# SIM808_RF.net
KiCad netlist of a schematic drawn in Altium Designer
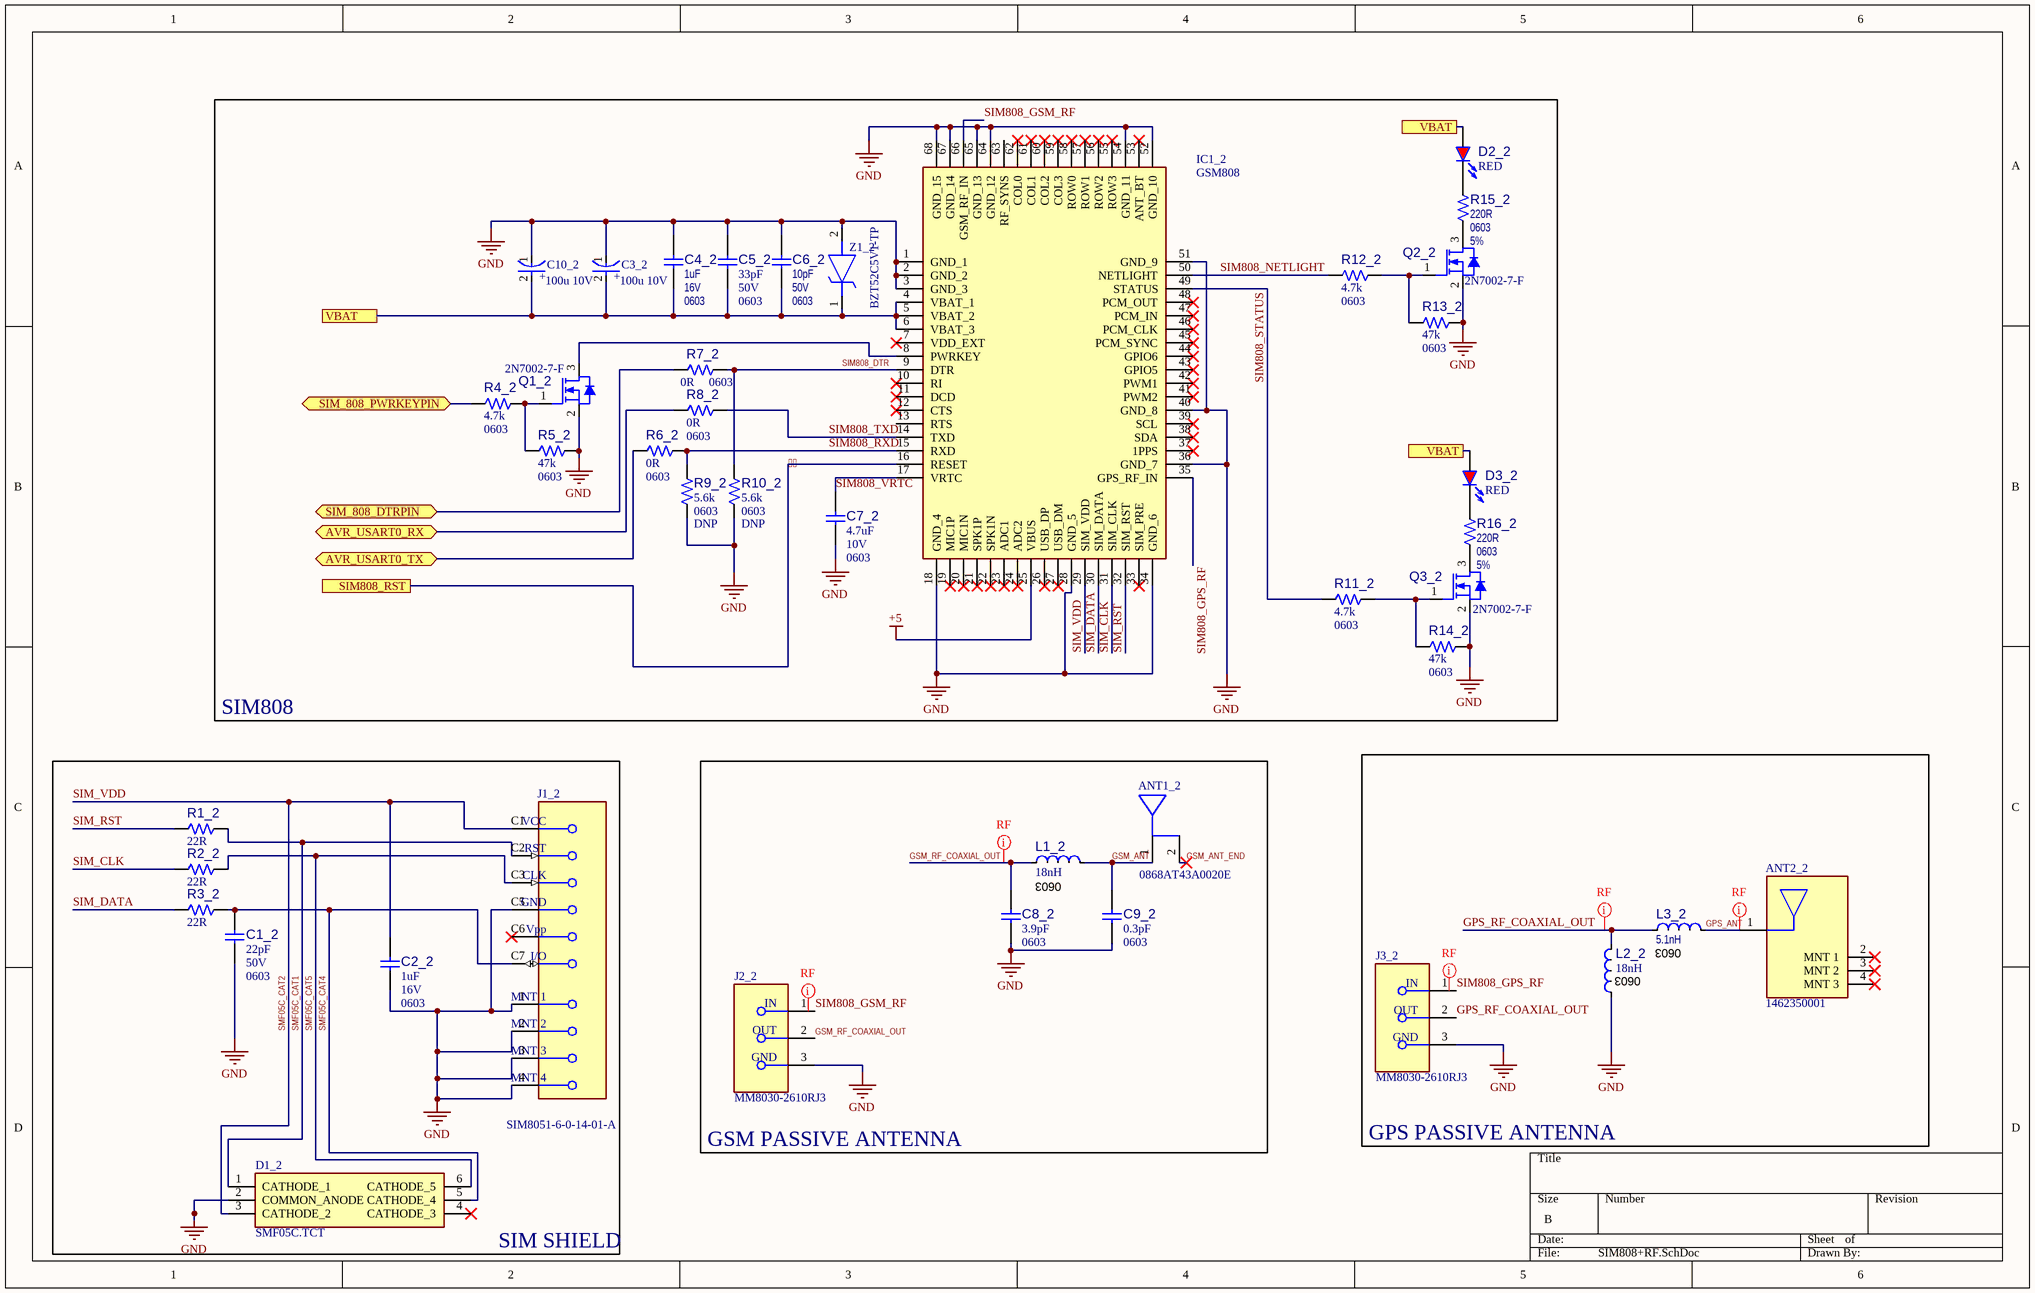
[diagram p0: SIM808+RF.SchDoc]

(export (version "E")
  (design (tool "Eeschema 10.0.6"))
  (components
    (comp (ref "ANT1_2")
      (value "0868AT43A0020E")
      (footprint "FP-0900AT43A0070E-MFG")
      (description "RF ANT CHIP SOLDER SMD")
      (libsource (lib "Altium Content Vault") (part "fdeedc8c81902f4dca238edc9264297"))
    )
    (comp (ref "ANT2_2")
      (value "1462350001")
      (footprint "FP-1462350001-MFG")
      (description "RF ANT 1.575GHZ MOLDED SLDR SMD")
      (fields
        (field (name "OCTOPART") "https://octopart.com/146235-0001-molex-75198029")
        (field (name "MANUFACTURER") "Molex")
      )
      (libsource (lib "Altium Content Vault") (part "44fa71a15c7cd8753818309cfbbf304"))
    )
    (comp (ref "C1_2")
      (value "22pF")
      (footprint "CAP_C_0603")
      (fields
        (field (name "VOLTAGE") "50V")
        (field (name "PACKAGE") "0603")
        (field (name "TOLERANCE") "5%")
        (field (name "Comment") "Capacitor NP")
      )
      (libsource (lib "MCHP-CDB") (part "Capacitor NP"))
    )
    (comp (ref "C2_2")
      (value "1uF")
      (footprint "CAP_C_0603")
      (fields
        (field (name "VOLTAGE") "16V")
        (field (name "PACKAGE") "0603")
        (field (name "TOLERANCE") "10%")
        (field (name "Comment") "Capacitor NP")
      )
      (libsource (lib "MCHP-CDB") (part "Capacitor NP"))
    )
    (comp (ref "C3_2")
      (value "100u 10V")
      (footprint "FP-TAJC-MFG")
      (description "100uF 10V  ±10% 1.2Ω 2312  SMD Tantalum Capacitor")
      (fields (field (name "TOLERANCE") "10%") (field (name "VOLTAGE") "10V"))
      (libsource (lib "Altium Content Vault") (part "203bc49f2ac43e59fd269a8c329ed05"))
    )
    (comp (ref "C4_2")
      (value "1uF")
      (footprint "CAP_C_0603")
      (fields
        (field (name "VOLTAGE") "16V")
        (field (name "PACKAGE") "0603")
        (field (name "TOLERANCE") "10%")
        (field (name "Comment") "Capacitor NP")
      )
      (libsource (lib "MCHP-CDB") (part "Capacitor NP"))
    )
    (comp (ref "C5_2")
      (value "33pF")
      (footprint "CAP_C_0603")
      (fields
        (field (name "VOLTAGE") "50V")
        (field (name "PACKAGE") "0603")
        (field (name "TOLERANCE") "5%")
        (field (name "Comment") "Capacitor NP")
      )
      (libsource (lib "MCHP-CDB") (part "Capacitor NP"))
    )
    (comp (ref "C6_2")
      (value "10pF")
      (footprint "CAP_C_0603")
      (fields
        (field (name "VOLTAGE") "50V")
        (field (name "PACKAGE") "0603")
        (field (name "TOLERANCE") "0.5pF")
        (field (name "Comment") "Capacitor NP")
        (field (name "OWNER") "Leah Whitaker")
      )
      (libsource (lib "MCHP-CDB") (part "Capacitor NP"))
    )
    (comp (ref "C7_2")
      (value "4.7uF")
      (footprint "CAP_C_0603")
      (fields
        (field (name "VOLTAGE") "10V")
        (field (name "PACKAGE") "0603")
        (field (name "TOLERANCE") "80%")
        (field (name "Comment") "Capacitor NP")
      )
      (libsource (lib "MCHP-CDB") (part "Capacitor NP"))
    )
    (comp (ref "C8_2")
      (value "3.9pF")
      (footprint "CAP_C_0603")
      (fields
        (field (name "PACKAGE") "0603")
        (field (name "TOLERANCE") "0.25pF")
        (field (name "Comment") "Capacitor NP")
      )
      (libsource (lib "MCHP-CDB") (part "Capacitor NP"))
    )
    (comp (ref "C9_2")
      (value "0.3pF")
      (footprint "CAP_C_0603")
      (fields
        (field (name "PACKAGE") "0603")
        (field (name "TOLERANCE") "0.25pF")
        (field (name "Comment") "Capacitor NP")
      )
      (libsource (lib "MCHP-CDB") (part "Capacitor NP"))
    )
    (comp (ref "C10_2")
      (value "100u 10V")
      (footprint "FP-TAJC-MFG")
      (description "100uF 10V  ±10% 1.2Ω 2312  SMD Tantalum Capacitor")
      (fields (field (name "TOLERANCE") "10%") (field (name "VOLTAGE") "10V"))
      (libsource (lib "Altium Content Vault") (part "203bc49f2ac43e59fd269a8c329ed05"))
    )
    (comp (ref "D1_2")
      (value "SMF05C.TCT")
      (footprint "SamacSys:SOT65P210X110-6N")
      (description "TVS Diode (Uni-directional)")
      (fields (field (name "MOUSER PART NUMBER") "947-SMF05C.TCT"))
      (libsource (lib "*") (part "SMF05C.TCT"))
    )
    (comp (ref "D2_2")
      (value "RED")
      (footprint "LED_0603_RED")
      (description "LED")
      (fields (field (name "POWER") "100mW") (field (name "Comment") "LED_red"))
      (libsource (lib "MCHP-CDB") (part "LED_red"))
    )
    (comp (ref "D3_2")
      (value "RED")
      (footprint "LED_0603_RED")
      (description "LED")
      (fields (field (name "POWER") "100mW") (field (name "Comment") "LED_red"))
      (libsource (lib "MCHP-CDB") (part "LED_red"))
    )
    (comp (ref "IC1_2")
      (value "GSM808")
      (footprint "SamacSys:GSM808")
      (description "Integrated Circuit")
      (libsource (lib "*") (part "GSM808"))
    )
    (comp (ref "J1_2")
      (value "SIM8051-6-0-14-01-A")
      (footprint "FP-SIM8051-6-0-14-01-A-MFG")
      (description "NANO SIM PUSH PULL, 6P, SMT, 1.3")
      (fields
        (field (name "MANUFACTURER") "GCT")
        (field (name "OCTOPART") "https://octopart.com/sim8051-6-0-14-01-a-gct-99340323")
      )
      (libsource (lib "Altium Content Vault") (part "3cc3b1fb44b6b07564fa90550f448b7"))
    )
    (comp (ref "J2_2")
      (value "MM8030-2610RJ3")
      (footprint "FP-MM8030-2610RJ3-MFG")
      (description "CONN SWG RCPT STR 50 OHM SMD")
      (libsource (lib "Altium Content Vault") (part "d3d0eca1eedd57daa0a06598d6096e1"))
    )
    (comp (ref "J3_2")
      (value "MM8030-2610RJ3")
      (footprint "FP-MM8030-2610RJ3-MFG")
      (description "CONN SWG RCPT STR 50 OHM SMD")
      (libsource (lib "Altium Content Vault") (part "d3d0eca1eedd57daa0a06598d6096e1"))
    )
    (comp (ref "L1_2")
      (value "18nH")
      (footprint "IND_C_0603")
      (description "Inductor")
      (libsource (lib "MCHP-CDB") (part "Inductor"))
    )
    (comp (ref "L2_2")
      (value "18nH")
      (footprint "IND_C_0603")
      (description "Inductor")
      (libsource (lib "MCHP-CDB") (part "Inductor"))
    )
    (comp (ref "L3_2")
      (value "5.1nH")
      (footprint "IND_C_0603")
      (description "Inductor")
      (fields (field (name "OWNER") "Gabor Bihari"))
      (libsource (lib "MCHP-CDB") (part "Inductor"))
    )
    (comp (ref "Q1_2")
      (value "2N7002-7-F")
      (footprint "SOT-23-3")
      (description "Transistor MOS")
      (fields
        (field (name "POWER") "370mW")
        (field (name "Comment") "Transistor MOS-N GSD")
        (field (name "OWNER") "Adrian M (M91404)")
      )
      (libsource (lib "MCHP-CDB") (part "Transistor MOS-N GSD"))
    )
    (comp (ref "Q2_2")
      (value "2N7002-7-F")
      (footprint "SOT-23-3")
      (description "Transistor MOS")
      (fields
        (field (name "POWER") "370mW")
        (field (name "Comment") "Transistor MOS-N GSD")
        (field (name "OWNER") "Adrian M (M91404)")
      )
      (libsource (lib "MCHP-CDB") (part "Transistor MOS-N GSD"))
    )
    (comp (ref "Q3_2")
      (value "2N7002-7-F")
      (footprint "SOT-23-3")
      (description "Transistor MOS")
      (fields
        (field (name "POWER") "370mW")
        (field (name "Comment") "Transistor MOS-N GSD")
        (field (name "OWNER") "Adrian M (M91404)")
      )
      (libsource (lib "MCHP-CDB") (part "Transistor MOS-N GSD"))
    )
    (comp (ref "R1_2")
      (value "22R")
      (footprint "RES_C_0603")
      (description "Resistor")
      (fields (field (name "VOLTAGE") "75V") (field (name "POWER") "1/10W"))
      (libsource (lib "MCHP-CDB") (part "Resistor"))
    )
    (comp (ref "R2_2")
      (value "22R")
      (footprint "RES_C_0603")
      (description "Resistor")
      (fields (field (name "VOLTAGE") "75V") (field (name "POWER") "1/10W"))
      (libsource (lib "MCHP-CDB") (part "Resistor"))
    )
    (comp (ref "R3_2")
      (value "22R")
      (footprint "RES_C_0603")
      (description "Resistor")
      (fields (field (name "VOLTAGE") "75V") (field (name "POWER") "1/10W"))
      (libsource (lib "MCHP-CDB") (part "Resistor"))
    )
    (comp (ref "R4_2")
      (value "4.7k")
      (footprint "RES_C_0603")
      (description "Resistor")
      (fields
        (field (name "PACKAGE") "0603")
        (field (name "VOLTAGE") "75V")
        (field (name "POWER") "1/10W")
        (field (name "OWNER") "Bogdan P (M91398)")
      )
      (libsource (lib "MCHP-CDB") (part "Resistor"))
    )
    (comp (ref "R5_2")
      (value "47k")
      (footprint "RES_C_0603")
      (description "Resistor")
      (fields
        (field (name "PACKAGE") "0603")
        (field (name "VOLTAGE") "75V")
        (field (name "POWER") "1/10W")
        (field (name "OWNER") "Adrian M (M91404)")
      )
      (libsource (lib "MCHP-CDB") (part "Resistor"))
    )
    (comp (ref "R6_2")
      (value "0R")
      (footprint "RES_C_0603")
      (description "Resistor")
      (fields
        (field (name "PACKAGE") "0603")
        (field (name "POWER") "1/10W")
        (field (name "OWNER") "Steve Dziaba")
      )
      (libsource (lib "MCHP-CDB") (part "Resistor"))
    )
    (comp (ref "R7_2")
      (value "0R")
      (footprint "RES_C_0603")
      (description "Resistor")
      (fields
        (field (name "PACKAGE") "0603")
        (field (name "POWER") "1/10W")
        (field (name "OWNER") "Steve Dziaba")
      )
      (libsource (lib "MCHP-CDB") (part "Resistor"))
    )
    (comp (ref "R8_2")
      (value "0R")
      (footprint "RES_C_0603")
      (description "Resistor")
      (fields
        (field (name "PACKAGE") "0603")
        (field (name "POWER") "1/10W")
        (field (name "OWNER") "Steve Dziaba")
      )
      (libsource (lib "MCHP-CDB") (part "Resistor"))
    )
    (comp (ref "R9_2")
      (value "5.6k")
      (footprint "RES_C_0603")
      (description "Resistor")
      (fields
        (field (name "PACKAGE") "0603")
        (field (name "VOLTAGE") "50V")
        (field (name "POWER") "1/10W")
        (field (name "POPULATED") "DNP")
      )
      (libsource (lib "MCHP-CDB") (part "Resistor"))
    )
    (comp (ref "R10_2")
      (value "5.6k")
      (footprint "RES_C_0603")
      (description "Resistor")
      (fields
        (field (name "PACKAGE") "0603")
        (field (name "VOLTAGE") "50V")
        (field (name "POWER") "1/10W")
        (field (name "POPULATED") "DNP")
      )
      (libsource (lib "MCHP-CDB") (part "Resistor"))
    )
    (comp (ref "R11_2")
      (value "4.7k")
      (footprint "RES_C_0603")
      (description "Resistor")
      (fields
        (field (name "PACKAGE") "0603")
        (field (name "VOLTAGE") "75V")
        (field (name "POWER") "1/10W")
        (field (name "OWNER") "Bogdan P (M91398)")
      )
      (libsource (lib "MCHP-CDB") (part "Resistor"))
    )
    (comp (ref "R12_2")
      (value "4.7k")
      (footprint "RES_C_0603")
      (description "Resistor")
      (fields
        (field (name "PACKAGE") "0603")
        (field (name "VOLTAGE") "75V")
        (field (name "POWER") "1/10W")
        (field (name "OWNER") "Bogdan P (M91398)")
      )
      (libsource (lib "MCHP-CDB") (part "Resistor"))
    )
    (comp (ref "R13_2")
      (value "47k")
      (footprint "RES_C_0603")
      (description "Resistor")
      (fields
        (field (name "PACKAGE") "0603")
        (field (name "VOLTAGE") "75V")
        (field (name "POWER") "1/10W")
        (field (name "OWNER") "Adrian M (M91404)")
      )
      (libsource (lib "MCHP-CDB") (part "Resistor"))
    )
    (comp (ref "R14_2")
      (value "47k")
      (footprint "RES_C_0603")
      (description "Resistor")
      (fields
        (field (name "PACKAGE") "0603")
        (field (name "VOLTAGE") "75V")
        (field (name "POWER") "1/10W")
        (field (name "OWNER") "Adrian M (M91404)")
      )
      (libsource (lib "MCHP-CDB") (part "Resistor"))
    )
    (comp (ref "R15_2")
      (value "220R")
      (footprint "RES_C_0603")
      (description "Resistor")
      (fields
        (field (name "PACKAGE") "0603")
        (field (name "TOLERANCE") "5%")
        (field (name "VOLTAGE") "50V")
        (field (name "POWER") "1/10W")
      )
      (libsource (lib "MCHP-CDB") (part "Resistor"))
    )
    (comp (ref "R16_2")
      (value "220R")
      (footprint "RES_C_0603")
      (description "Resistor")
      (fields
        (field (name "PACKAGE") "0603")
        (field (name "TOLERANCE") "5%")
        (field (name "VOLTAGE") "50V")
        (field (name "POWER") "1/10W")
      )
      (libsource (lib "MCHP-CDB") (part "Resistor"))
    )
    (comp (ref "Z1_2")
      (value "BZT52C5V1-TP")
      (footprint "SamacSys:SOD3716X135N")
      (description "Zener Diode")
      (fields (field (name "MOUSER PART NUMBER") "833-BZT52C5V1-TP"))
      (libsource (lib "*") (part "BZT52C5V1-TP"))
    )
  )
  (nets
    (net (code "1") (name "+5") (class "Default")
      (node (ref "IC1_2") (pin "25") (pinfunction "VBUS_25") (pintype "passive"))
    )
    (net (code "2") (name "/") (class "Default")
      (node (ref "IC1_2") (pin "16") (pinfunction "RESET_16") (pintype "passive"))
    )
    (net (code "3") (name "/AVR_USART0_RX") (class "Default")
      (node (ref "R8_2") (pin "1") (pinfunction "1_1") (pintype "passive"))
    )
    (net (code "4") (name "/AVR_USART0_TX") (class "Default")
      (node (ref "R6_2") (pin "1") (pinfunction "1_1") (pintype "passive"))
    )
    (net (code "5") (name "/GPS_ANT") (class "Default")
      (node (ref "ANT2_2") (pin "1") (pinfunction "FEEDING_PAD_1") (pintype "passive"))
      (node (ref "L3_2") (pin "2") (pinfunction "F_2") (pintype "passive"))
    )
    (net (code "6") (name "/GPS_RF_COAXIAL_OUT") (class "Default")
      (node (ref "J3_2") (pin "2") (pinfunction "OUT_2") (pintype "passive"))
      (node (ref "L2_2") (pin "2") (pinfunction "F_2") (pintype "passive"))
      (node (ref "L3_2") (pin "1") (pinfunction "S_1") (pintype "passive"))
    )
    (net (code "7") (name "/GSM_ANT") (class "Default")
      (node (ref "ANT1_2") (pin "1") (pinfunction "RF_Feeding_Point_1") (pintype "passive"))
      (node (ref "C9_2") (pin "2") (pinfunction "2_2") (pintype "passive"))
      (node (ref "L1_2") (pin "2") (pinfunction "F_2") (pintype "passive"))
    )
    (net (code "8") (name "/GSM_ANT_END") (class "Default")
      (node (ref "ANT1_2") (pin "2") (pinfunction "To_trace_element_2") (pintype "passive+no_connect"))
    )
    (net (code "9") (name "/GSM_RF_COAXIAL_OUT") (class "Default")
      (node (ref "C8_2") (pin "2") (pinfunction "2_2") (pintype "passive"))
      (node (ref "J2_2") (pin "2") (pinfunction "OUT_2") (pintype "passive"))
      (node (ref "L1_2") (pin "1") (pinfunction "S_1") (pintype "passive"))
    )
    (net (code "10") (name "/SIM808_DTR") (class "Default")
      (node (ref "IC1_2") (pin "9") (pinfunction "DTR_9") (pintype "passive"))
      (node (ref "R10_2") (pin "2") (pinfunction "2_2") (pintype "passive"))
      (node (ref "R7_2") (pin "2") (pinfunction "2_2") (pintype "passive"))
    )
    (net (code "11") (name "/SIM808_GPS_RF") (class "Default")
      (node (ref "IC1_2") (pin "35") (pinfunction "GPS_RF_IN_35") (pintype "passive"))
      (node (ref "J3_2") (pin "1") (pinfunction "IN_1") (pintype "passive"))
    )
    (net (code "12") (name "/SIM808_GSM_RF") (class "Default")
      (node (ref "IC1_2") (pin "66") (pinfunction "GSM_RF_IN_66") (pintype "passive"))
      (node (ref "J2_2") (pin "1") (pinfunction "IN_1") (pintype "passive"))
    )
    (net (code "13") (name "/SIM808_NETLIGHT") (class "Default")
      (node (ref "IC1_2") (pin "50") (pinfunction "NETLIGHT_50") (pintype "passive"))
      (node (ref "R12_2") (pin "1") (pinfunction "1_1") (pintype "passive"))
    )
    (net (code "14") (name "/SIM808_RXD") (class "Default")
      (node (ref "IC1_2") (pin "15") (pinfunction "RXD_15") (pintype "passive"))
      (node (ref "R6_2") (pin "2") (pinfunction "2_2") (pintype "passive"))
      (node (ref "R9_2") (pin "2") (pinfunction "2_2") (pintype "passive"))
    )
    (net (code "15") (name "/SIM808_STATUS") (class "Default")
      (node (ref "IC1_2") (pin "49") (pinfunction "STATUS_49") (pintype "passive"))
      (node (ref "R11_2") (pin "1") (pinfunction "1_1") (pintype "passive"))
    )
    (net (code "16") (name "/SIM808_TXD") (class "Default")
      (node (ref "IC1_2") (pin "14") (pinfunction "TXD_14") (pintype "passive"))
      (node (ref "R8_2") (pin "2") (pinfunction "2_2") (pintype "passive"))
    )
    (net (code "17") (name "/SIM808_VRTC") (class "Default")
      (node (ref "C7_2") (pin "2") (pinfunction "2_2") (pintype "passive"))
      (node (ref "IC1_2") (pin "17") (pinfunction "VRTC_17") (pintype "passive"))
    )
    (net (code "18") (name "/SIM_808_DTRPIN") (class "Default")
      (node (ref "R7_2") (pin "1") (pinfunction "1_1") (pintype "passive"))
    )
    (net (code "19") (name "/SIM_808_PWRKEYPIN") (class "Default")
      (node (ref "R4_2") (pin "1") (pinfunction "1_1") (pintype "passive"))
    )
    (net (code "20") (name "/SIM_CLK") (class "Default")
      (node (ref "IC1_2") (pin "31") (pinfunction "SIM_CLK_31") (pintype "passive"))
      (node (ref "R2_2") (pin "1") (pinfunction "1_1") (pintype "passive"))
    )
    (net (code "21") (name "/SIM_DATA") (class "Default")
      (node (ref "IC1_2") (pin "30") (pinfunction "SIM_DATA_30") (pintype "passive"))
      (node (ref "R3_2") (pin "1") (pinfunction "1_1") (pintype "passive"))
    )
    (net (code "22") (name "/SIM_RST") (class "Default")
      (node (ref "IC1_2") (pin "32") (pinfunction "SIM_RST_32") (pintype "passive"))
      (node (ref "R1_2") (pin "1") (pinfunction "1_1") (pintype "passive"))
    )
    (net (code "23") (name "/SIM_VDD") (class "Default")
      (node (ref "C2_2") (pin "2") (pinfunction "2_2") (pintype "passive"))
      (node (ref "D1_2") (pin "3") (pinfunction "CATHODE_2_3") (pintype "passive"))
      (node (ref "IC1_2") (pin "29") (pinfunction "SIM_VDD_29") (pintype "passive"))
      (node (ref "J1_2") (pin "C1") (pinfunction "VCC_C1") (pintype "power_in"))
    )
    (net (code "24") (name "/SMF05C_CAT1") (class "Default")
      (node (ref "D1_2") (pin "1") (pinfunction "CATHODE_1_1") (pintype "passive"))
      (node (ref "J1_2") (pin "C2") (pinfunction "RST_C2") (pintype "input"))
      (node (ref "R1_2") (pin "2") (pinfunction "2_2") (pintype "passive"))
    )
    (net (code "25") (name "/SMF05C_CAT4") (class "Default")
      (node (ref "C1_2") (pin "2") (pinfunction "2_2") (pintype "passive"))
      (node (ref "D1_2") (pin "5") (pinfunction "CATHODE_4_5") (pintype "passive"))
      (node (ref "J1_2") (pin "C7") (pinfunction "I/O_C7") (pintype "bidirectional"))
      (node (ref "R3_2") (pin "2") (pinfunction "2_2") (pintype "passive"))
    )
    (net (code "26") (name "/SMF05C_CAT5") (class "Default")
      (node (ref "D1_2") (pin "6") (pinfunction "CATHODE_5_6") (pintype "passive"))
      (node (ref "J1_2") (pin "C3") (pinfunction "CLK_C3") (pintype "input"))
      (node (ref "R2_2") (pin "2") (pinfunction "2_2") (pintype "passive"))
    )
    (net (code "27") (name "/VBAT") (class "Default")
      (node (ref "C10_2") (pin "2") (pinfunction "A_2") (pintype "passive"))
      (node (ref "C3_2") (pin "2") (pinfunction "A_2") (pintype "passive"))
      (node (ref "C4_2") (pin "1") (pinfunction "1_1") (pintype "passive"))
      (node (ref "C5_2") (pin "2") (pinfunction "2_2") (pintype "passive"))
      (node (ref "C6_2") (pin "1") (pinfunction "1_1") (pintype "passive"))
      (node (ref "D2_2") (pin "1") (pinfunction "A_1") (pintype "passive"))
      (node (ref "D3_2") (pin "1") (pinfunction "A_1") (pintype "passive"))
      (node (ref "IC1_2") (pin "4") (pinfunction "VBAT_1_4") (pintype "passive"))
      (node (ref "IC1_2") (pin "5") (pinfunction "VBAT_2_5") (pintype "passive"))
      (node (ref "IC1_2") (pin "6") (pinfunction "VBAT_3_6") (pintype "passive"))
      (node (ref "Z1_2") (pin "1") (pinfunction "K_1") (pintype "passive"))
    )
    (net (code "28") (name "GND") (class "Default")
      (node (ref "C10_2") (pin "1") (pinfunction "C_1") (pintype "passive"))
      (node (ref "C1_2") (pin "1") (pinfunction "1_1") (pintype "passive"))
      (node (ref "C2_2") (pin "1") (pinfunction "1_1") (pintype "passive"))
      (node (ref "C3_2") (pin "1") (pinfunction "C_1") (pintype "passive"))
      (node (ref "C4_2") (pin "2") (pinfunction "2_2") (pintype "passive"))
      (node (ref "C5_2") (pin "1") (pinfunction "1_1") (pintype "passive"))
      (node (ref "C6_2") (pin "2") (pinfunction "2_2") (pintype "passive"))
      (node (ref "C7_2") (pin "1") (pinfunction "1_1") (pintype "passive"))
      (node (ref "C8_2") (pin "1") (pinfunction "1_1") (pintype "passive"))
      (node (ref "C9_2") (pin "1") (pinfunction "1_1") (pintype "passive"))
      (node (ref "D1_2") (pin "2") (pinfunction "COMMON_ANODE_2") (pintype "passive"))
      (node (ref "IC1_2") (pin "1") (pinfunction "GND_1_1") (pintype "passive"))
      (node (ref "IC1_2") (pin "18") (pinfunction "GND_4_18") (pintype "passive"))
      (node (ref "IC1_2") (pin "2") (pinfunction "GND_2_2") (pintype "passive"))
      (node (ref "IC1_2") (pin "28") (pinfunction "GND_5_28") (pintype "passive"))
      (node (ref "IC1_2") (pin "3") (pinfunction "GND_3_3") (pintype "passive"))
      (node (ref "IC1_2") (pin "34") (pinfunction "GND_6_34") (pintype "passive"))
      (node (ref "IC1_2") (pin "36") (pinfunction "GND_7_36") (pintype "passive"))
      (node (ref "IC1_2") (pin "40") (pinfunction "GND_8_40") (pintype "passive"))
      (node (ref "IC1_2") (pin "51") (pinfunction "GND_9_51") (pintype "passive"))
      (node (ref "IC1_2") (pin "52") (pinfunction "GND_10_52") (pintype "passive"))
      (node (ref "IC1_2") (pin "54") (pinfunction "GND_11_54") (pintype "passive"))
      (node (ref "IC1_2") (pin "64") (pinfunction "GND_12_64") (pintype "passive"))
      (node (ref "IC1_2") (pin "65") (pinfunction "GND_13_65") (pintype "passive"))
      (node (ref "IC1_2") (pin "67") (pinfunction "GND_14_67") (pintype "passive"))
      (node (ref "IC1_2") (pin "68") (pinfunction "GND_15_68") (pintype "passive"))
      (node (ref "J1_2") (pin "1") (pinfunction "MNT_1_1") (pintype "passive"))
      (node (ref "J1_2") (pin "2") (pinfunction "MNT_2_2") (pintype "passive"))
      (node (ref "J1_2") (pin "3") (pinfunction "MNT_3_3") (pintype "passive"))
      (node (ref "J1_2") (pin "4") (pinfunction "MNT_4_4") (pintype "passive"))
      (node (ref "J1_2") (pin "C5") (pinfunction "GND_C5") (pintype "power_in"))
      (node (ref "J2_2") (pin "3") (pinfunction "GND_3") (pintype "passive"))
      (node (ref "J3_2") (pin "3") (pinfunction "GND_3") (pintype "passive"))
      (node (ref "L2_2") (pin "1") (pinfunction "S_1") (pintype "passive"))
      (node (ref "Q1_2") (pin "2") (pinfunction "S_2") (pintype "passive"))
      (node (ref "Q2_2") (pin "2") (pinfunction "S_2") (pintype "passive"))
      (node (ref "Q3_2") (pin "2") (pinfunction "S_2") (pintype "passive"))
      (node (ref "R10_2") (pin "1") (pinfunction "1_1") (pintype "passive"))
      (node (ref "R13_2") (pin "2") (pinfunction "2_2") (pintype "passive"))
      (node (ref "R14_2") (pin "2") (pinfunction "2_2") (pintype "passive"))
      (node (ref "R5_2") (pin "2") (pinfunction "2_2") (pintype "passive"))
      (node (ref "R9_2") (pin "1") (pinfunction "1_1") (pintype "passive"))
      (node (ref "Z1_2") (pin "2") (pinfunction "A_2") (pintype "passive"))
    )
    (net (code "29") (name "Net-(D2_2-K)") (class "Default")
      (node (ref "D2_2") (pin "2") (pinfunction "K_2") (pintype "passive"))
      (node (ref "R15_2") (pin "2") (pinfunction "2_2") (pintype "passive"))
    )
    (net (code "30") (name "Net-(D3_2-K)") (class "Default")
      (node (ref "D3_2") (pin "2") (pinfunction "K_2") (pintype "passive"))
      (node (ref "R16_2") (pin "2") (pinfunction "2_2") (pintype "passive"))
    )
    (net (code "31") (name "Net-(IC1_2-PWRKEY)") (class "Default")
      (node (ref "IC1_2") (pin "8") (pinfunction "PWRKEY_8") (pintype "passive"))
      (node (ref "Q1_2") (pin "3") (pinfunction "D_3") (pintype "passive"))
    )
    (net (code "32") (name "Net-(Q1_2-G)") (class "Default")
      (node (ref "Q1_2") (pin "1") (pinfunction "G_1") (pintype "passive"))
      (node (ref "R4_2") (pin "2") (pinfunction "2_2") (pintype "passive"))
      (node (ref "R5_2") (pin "1") (pinfunction "1_1") (pintype "passive"))
    )
    (net (code "33") (name "Net-(Q2_2-D)") (class "Default")
      (node (ref "Q2_2") (pin "3") (pinfunction "D_3") (pintype "passive"))
      (node (ref "R15_2") (pin "1") (pinfunction "1_1") (pintype "passive"))
    )
    (net (code "34") (name "Net-(Q2_2-G)") (class "Default")
      (node (ref "Q2_2") (pin "1") (pinfunction "G_1") (pintype "passive"))
      (node (ref "R12_2") (pin "2") (pinfunction "2_2") (pintype "passive"))
      (node (ref "R13_2") (pin "1") (pinfunction "1_1") (pintype "passive"))
    )
    (net (code "35") (name "Net-(Q3_2-D)") (class "Default")
      (node (ref "Q3_2") (pin "3") (pinfunction "D_3") (pintype "passive"))
      (node (ref "R16_2") (pin "1") (pinfunction "1_1") (pintype "passive"))
    )
    (net (code "36") (name "Net-(Q3_2-G)") (class "Default")
      (node (ref "Q3_2") (pin "1") (pinfunction "G_1") (pintype "passive"))
      (node (ref "R11_2") (pin "2") (pinfunction "2_2") (pintype "passive"))
      (node (ref "R14_2") (pin "1") (pinfunction "1_1") (pintype "passive"))
    )
    (net (code "37") (name "unconnected-(ANT2_2-MNT_1-Pad2)") (class "Default")
      (node (ref "ANT2_2") (pin "2") (pinfunction "MNT_1_2") (pintype "passive+no_connect"))
    )
    (net (code "38") (name "unconnected-(ANT2_2-MNT_2-Pad3)") (class "Default")
      (node (ref "ANT2_2") (pin "3") (pinfunction "MNT_2_3") (pintype "passive+no_connect"))
    )
    (net (code "39") (name "unconnected-(ANT2_2-MNT_3-Pad4)") (class "Default")
      (node (ref "ANT2_2") (pin "4") (pinfunction "MNT_3_4") (pintype "passive+no_connect"))
    )
    (net (code "40") (name "unconnected-(D1_2-CATHODE_3-Pad4)") (class "Default")
      (node (ref "D1_2") (pin "4") (pinfunction "CATHODE_3_4") (pintype "passive+no_connect"))
    )
    (net (code "41") (name "unconnected-(IC1_2-1PPS-Pad37)") (class "Default")
      (node (ref "IC1_2") (pin "37") (pinfunction "1PPS_37") (pintype "passive+no_connect"))
    )
    (net (code "42") (name "unconnected-(IC1_2-ADC1-Pad23)") (class "Default")
      (node (ref "IC1_2") (pin "23") (pinfunction "ADC1_23") (pintype "passive+no_connect"))
    )
    (net (code "43") (name "unconnected-(IC1_2-ADC2-Pad24)") (class "Default")
      (node (ref "IC1_2") (pin "24") (pinfunction "ADC2_24") (pintype "passive+no_connect"))
    )
    (net (code "44") (name "unconnected-(IC1_2-ANT_BT-Pad53)") (class "Default")
      (node (ref "IC1_2") (pin "53") (pinfunction "ANT_BT_53") (pintype "passive+no_connect"))
    )
    (net (code "45") (name "unconnected-(IC1_2-COL0-Pad62)") (class "Default")
      (node (ref "IC1_2") (pin "62") (pinfunction "COL0_62") (pintype "passive+no_connect"))
    )
    (net (code "46") (name "unconnected-(IC1_2-COL1-Pad61)") (class "Default")
      (node (ref "IC1_2") (pin "61") (pinfunction "COL1_61") (pintype "passive+no_connect"))
    )
    (net (code "47") (name "unconnected-(IC1_2-COL2-Pad60)") (class "Default")
      (node (ref "IC1_2") (pin "60") (pinfunction "COL2_60") (pintype "passive+no_connect"))
    )
    (net (code "48") (name "unconnected-(IC1_2-COL3-Pad59)") (class "Default")
      (node (ref "IC1_2") (pin "59") (pinfunction "COL3_59") (pintype "passive+no_connect"))
    )
    (net (code "49") (name "unconnected-(IC1_2-CTS-Pad12)") (class "Default")
      (node (ref "IC1_2") (pin "12") (pinfunction "CTS_12") (pintype "passive+no_connect"))
    )
    (net (code "50") (name "unconnected-(IC1_2-DCD-Pad11)") (class "Default")
      (node (ref "IC1_2") (pin "11") (pinfunction "DCD_11") (pintype "passive+no_connect"))
    )
    (net (code "51") (name "unconnected-(IC1_2-GPIO5-Pad43)") (class "Default")
      (node (ref "IC1_2") (pin "43") (pinfunction "GPIO5_43") (pintype "passive+no_connect"))
    )
    (net (code "52") (name "unconnected-(IC1_2-GPIO6-Pad44)") (class "Default")
      (node (ref "IC1_2") (pin "44") (pinfunction "GPIO6_44") (pintype "passive+no_connect"))
    )
    (net (code "53") (name "unconnected-(IC1_2-MIC1N-Pad20)") (class "Default")
      (node (ref "IC1_2") (pin "20") (pinfunction "MIC1N_20") (pintype "passive+no_connect"))
    )
    (net (code "54") (name "unconnected-(IC1_2-MIC1P-Pad19)") (class "Default")
      (node (ref "IC1_2") (pin "19") (pinfunction "MIC1P_19") (pintype "passive+no_connect"))
    )
    (net (code "55") (name "unconnected-(IC1_2-PCM_CLK-Pad46)") (class "Default")
      (node (ref "IC1_2") (pin "46") (pinfunction "PCM_CLK_46") (pintype "passive+no_connect"))
    )
    (net (code "56") (name "unconnected-(IC1_2-PCM_IN-Pad47)") (class "Default")
      (node (ref "IC1_2") (pin "47") (pinfunction "PCM_IN_47") (pintype "passive+no_connect"))
    )
    (net (code "57") (name "unconnected-(IC1_2-PCM_OUT-Pad48)") (class "Default")
      (node (ref "IC1_2") (pin "48") (pinfunction "PCM_OUT_48") (pintype "passive+no_connect"))
    )
    (net (code "58") (name "unconnected-(IC1_2-PCM_SYNC-Pad45)") (class "Default")
      (node (ref "IC1_2") (pin "45") (pinfunction "PCM_SYNC_45") (pintype "passive+no_connect"))
    )
    (net (code "59") (name "unconnected-(IC1_2-PWM1-Pad42)") (class "Default")
      (node (ref "IC1_2") (pin "42") (pinfunction "PWM1_42") (pintype "passive+no_connect"))
    )
    (net (code "60") (name "unconnected-(IC1_2-PWM2-Pad41)") (class "Default")
      (node (ref "IC1_2") (pin "41") (pinfunction "PWM2_41") (pintype "passive+no_connect"))
    )
    (net (code "61") (name "unconnected-(IC1_2-RF_SYNS-Pad63)") (class "Default")
      (node (ref "IC1_2") (pin "63") (pinfunction "RF_SYNS_63") (pintype "passive"))
    )
    (net (code "62") (name "unconnected-(IC1_2-RI-Pad10)") (class "Default")
      (node (ref "IC1_2") (pin "10") (pinfunction "RI_10") (pintype "passive+no_connect"))
    )
    (net (code "63") (name "unconnected-(IC1_2-ROW0-Pad58)") (class "Default")
      (node (ref "IC1_2") (pin "58") (pinfunction "ROW0_58") (pintype "passive+no_connect"))
    )
    (net (code "64") (name "unconnected-(IC1_2-ROW1-Pad57)") (class "Default")
      (node (ref "IC1_2") (pin "57") (pinfunction "ROW1_57") (pintype "passive+no_connect"))
    )
    (net (code "65") (name "unconnected-(IC1_2-ROW2-Pad56)") (class "Default")
      (node (ref "IC1_2") (pin "56") (pinfunction "ROW2_56") (pintype "passive+no_connect"))
    )
    (net (code "66") (name "unconnected-(IC1_2-ROW3-Pad55)") (class "Default")
      (node (ref "IC1_2") (pin "55") (pinfunction "ROW3_55") (pintype "passive+no_connect"))
    )
    (net (code "67") (name "unconnected-(IC1_2-RTS-Pad13)") (class "Default")
      (node (ref "IC1_2") (pin "13") (pinfunction "RTS_13") (pintype "passive"))
    )
    (net (code "68") (name "unconnected-(IC1_2-SCL-Pad39)") (class "Default")
      (node (ref "IC1_2") (pin "39") (pinfunction "SCL_39") (pintype "passive+no_connect"))
    )
    (net (code "69") (name "unconnected-(IC1_2-SDA-Pad38)") (class "Default")
      (node (ref "IC1_2") (pin "38") (pinfunction "SDA_38") (pintype "passive+no_connect"))
    )
    (net (code "70") (name "unconnected-(IC1_2-SIM_PRE-Pad33)") (class "Default")
      (node (ref "IC1_2") (pin "33") (pinfunction "SIM_PRE_33") (pintype "passive+no_connect"))
    )
    (net (code "71") (name "unconnected-(IC1_2-SPK1N-Pad22)") (class "Default")
      (node (ref "IC1_2") (pin "22") (pinfunction "SPK1N_22") (pintype "passive+no_connect"))
    )
    (net (code "72") (name "unconnected-(IC1_2-SPK1P-Pad21)") (class "Default")
      (node (ref "IC1_2") (pin "21") (pinfunction "SPK1P_21") (pintype "passive+no_connect"))
    )
    (net (code "73") (name "unconnected-(IC1_2-USB_DM-Pad27)") (class "Default")
      (node (ref "IC1_2") (pin "27") (pinfunction "USB_DM_27") (pintype "passive+no_connect"))
    )
    (net (code "74") (name "unconnected-(IC1_2-USB_DP-Pad26)") (class "Default")
      (node (ref "IC1_2") (pin "26") (pinfunction "USB_DP_26") (pintype "passive+no_connect"))
    )
    (net (code "75") (name "unconnected-(IC1_2-VDD_EXT-Pad7)") (class "Default")
      (node (ref "IC1_2") (pin "7") (pinfunction "VDD_EXT_7") (pintype "passive+no_connect"))
    )
    (net (code "76") (name "unconnected-(J1_2-Vpp-PadC6)") (class "Default")
      (node (ref "J1_2") (pin "C6") (pinfunction "Vpp_C6") (pintype "power_in+no_connect"))
    )
  )
)
